# r202smt.net
KiCad netlist of a schematic drawn in EAGLE
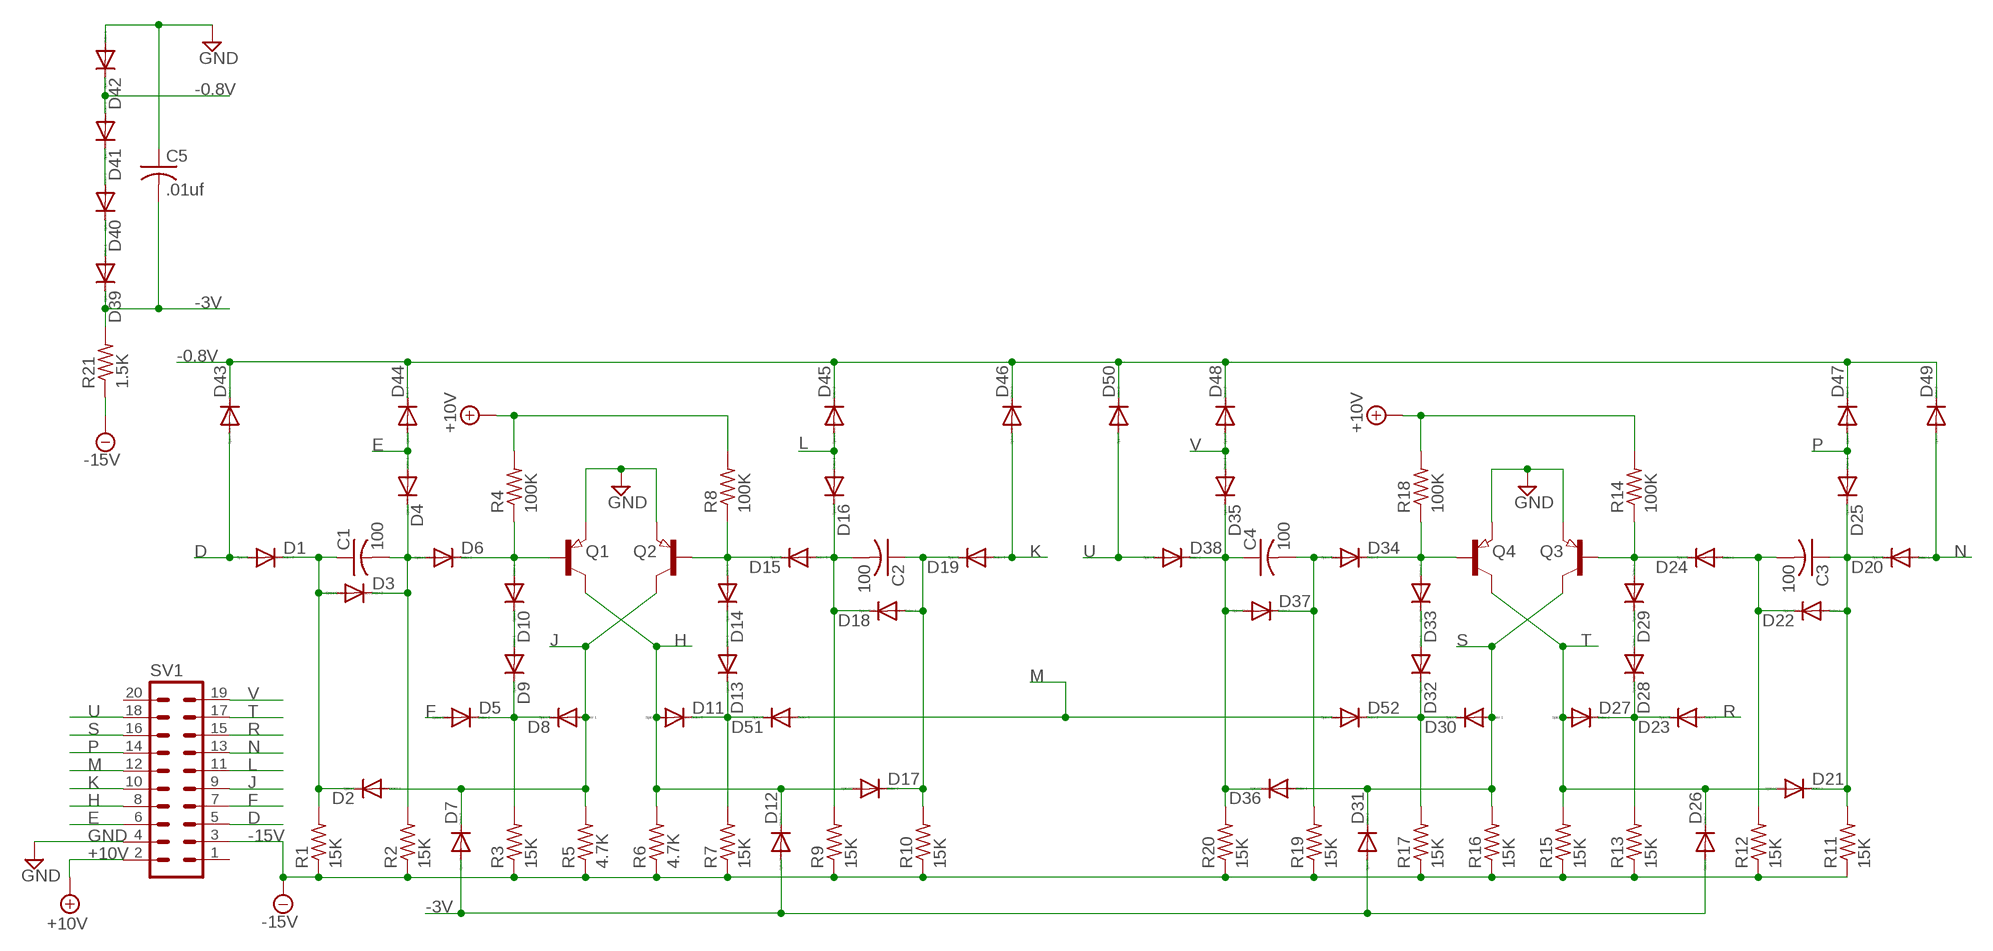
[diagram p0: schematic, sheet 1]

(export (version "E")
  (design (tool "Eeschema 10.0.6"))
  (components
    (comp (ref "C1")
      (value "100")
      (footprint "eagle-import:C0603")
      (libsource (lib "eagle-import") (part "C-USC0603"))
    )
    (comp (ref "C2")
      (value "100")
      (footprint "eagle-import:C0603")
      (libsource (lib "eagle-import") (part "C-USC0603"))
    )
    (comp (ref "C3")
      (value "100")
      (footprint "eagle-import:C0603")
      (libsource (lib "eagle-import") (part "C-USC0603"))
    )
    (comp (ref "C4")
      (value "100")
      (footprint "eagle-import:C0603")
      (libsource (lib "eagle-import") (part "C-USC0603"))
    )
    (comp (ref "C5")
      (value ".01uf")
      (footprint "eagle-import:C1206")
      (libsource (lib "eagle-import") (part "C-USC1206"))
    )
    (comp (ref "D1")
      (value "DIODE-SOD110-W")
      (footprint "eagle-import:SOD110-W")
      (libsource (lib "eagle-import") (part "DIODE-SOD110-W"))
    )
    (comp (ref "D2")
      (value "DIODE-SOD110-W")
      (footprint "eagle-import:SOD110-W")
      (libsource (lib "eagle-import") (part "DIODE-SOD110-W"))
    )
    (comp (ref "D3")
      (value "DIODE-SOD110-W")
      (footprint "eagle-import:SOD110-W")
      (libsource (lib "eagle-import") (part "DIODE-SOD110-W"))
    )
    (comp (ref "D4")
      (value "DIODE-SOD110-W")
      (footprint "eagle-import:SOD110-W")
      (libsource (lib "eagle-import") (part "DIODE-SOD110-W"))
    )
    (comp (ref "D5")
      (value "DIODE-SOD110-W")
      (footprint "eagle-import:SOD110-W")
      (libsource (lib "eagle-import") (part "DIODE-SOD110-W"))
    )
    (comp (ref "D6")
      (value "DIODE-SOD110-W")
      (footprint "eagle-import:SOD110-W")
      (libsource (lib "eagle-import") (part "DIODE-SOD110-W"))
    )
    (comp (ref "D7")
      (value "DIODE-SOD110-W")
      (footprint "eagle-import:SOD110-W")
      (libsource (lib "eagle-import") (part "DIODE-SOD110-W"))
    )
    (comp (ref "D8")
      (value "DIODE-SOD110-W")
      (footprint "eagle-import:SOD110-W")
      (libsource (lib "eagle-import") (part "DIODE-SOD110-W"))
    )
    (comp (ref "D9")
      (value "DIODE-SOD110-W")
      (footprint "eagle-import:SOD110-W")
      (libsource (lib "eagle-import") (part "DIODE-SOD110-W"))
    )
    (comp (ref "D10")
      (value "DIODE-SOD110-W")
      (footprint "eagle-import:SOD110-W")
      (libsource (lib "eagle-import") (part "DIODE-SOD110-W"))
    )
    (comp (ref "D11")
      (value "DIODE-SOD110-W")
      (footprint "eagle-import:SOD110-W")
      (libsource (lib "eagle-import") (part "DIODE-SOD110-W"))
    )
    (comp (ref "D12")
      (value "DIODE-SOD110-W")
      (footprint "eagle-import:SOD110-W")
      (libsource (lib "eagle-import") (part "DIODE-SOD110-W"))
    )
    (comp (ref "D13")
      (value "DIODE-SOD110-W")
      (footprint "eagle-import:SOD110-W")
      (libsource (lib "eagle-import") (part "DIODE-SOD110-W"))
    )
    (comp (ref "D14")
      (value "DIODE-SOD110-W")
      (footprint "eagle-import:SOD110-W")
      (libsource (lib "eagle-import") (part "DIODE-SOD110-W"))
    )
    (comp (ref "D15")
      (value "DIODE-SOD110-W")
      (footprint "eagle-import:SOD110-W")
      (libsource (lib "eagle-import") (part "DIODE-SOD110-W"))
    )
    (comp (ref "D16")
      (value "DIODE-SOD110-W")
      (footprint "eagle-import:SOD110-W")
      (libsource (lib "eagle-import") (part "DIODE-SOD110-W"))
    )
    (comp (ref "D17")
      (value "DIODE-SOD110-W")
      (footprint "eagle-import:SOD110-W")
      (libsource (lib "eagle-import") (part "DIODE-SOD110-W"))
    )
    (comp (ref "D18")
      (value "DIODE-SOD110-W")
      (footprint "eagle-import:SOD110-W")
      (libsource (lib "eagle-import") (part "DIODE-SOD110-W"))
    )
    (comp (ref "D19")
      (value "DIODE-SOD110-W")
      (footprint "eagle-import:SOD110-W")
      (libsource (lib "eagle-import") (part "DIODE-SOD110-W"))
    )
    (comp (ref "D20")
      (value "DIODE-SOD110-W")
      (footprint "eagle-import:SOD110-W")
      (libsource (lib "eagle-import") (part "DIODE-SOD110-W"))
    )
    (comp (ref "D21")
      (value "DIODE-SOD110-W")
      (footprint "eagle-import:SOD110-W")
      (libsource (lib "eagle-import") (part "DIODE-SOD110-W"))
    )
    (comp (ref "D22")
      (value "DIODE-SOD110-W")
      (footprint "eagle-import:SOD110-W")
      (libsource (lib "eagle-import") (part "DIODE-SOD110-W"))
    )
    (comp (ref "D23")
      (value "DIODE-SOD110-W")
      (footprint "eagle-import:SOD110-W")
      (libsource (lib "eagle-import") (part "DIODE-SOD110-W"))
    )
    (comp (ref "D24")
      (value "DIODE-SOD110-W")
      (footprint "eagle-import:SOD110-W")
      (libsource (lib "eagle-import") (part "DIODE-SOD110-W"))
    )
    (comp (ref "D25")
      (value "DIODE-SOD110-W")
      (footprint "eagle-import:SOD110-W")
      (libsource (lib "eagle-import") (part "DIODE-SOD110-W"))
    )
    (comp (ref "D26")
      (value "DIODE-SOD110-W")
      (footprint "eagle-import:SOD110-W")
      (libsource (lib "eagle-import") (part "DIODE-SOD110-W"))
    )
    (comp (ref "D27")
      (value "DIODE-SOD110-W")
      (footprint "eagle-import:SOD110-W")
      (libsource (lib "eagle-import") (part "DIODE-SOD110-W"))
    )
    (comp (ref "D28")
      (value "DIODE-SOD110-W")
      (footprint "eagle-import:SOD110-W")
      (libsource (lib "eagle-import") (part "DIODE-SOD110-W"))
    )
    (comp (ref "D29")
      (value "DIODE-SOD110-W")
      (footprint "eagle-import:SOD110-W")
      (libsource (lib "eagle-import") (part "DIODE-SOD110-W"))
    )
    (comp (ref "D30")
      (value "DIODE-SOD110-W")
      (footprint "eagle-import:SOD110-W")
      (libsource (lib "eagle-import") (part "DIODE-SOD110-W"))
    )
    (comp (ref "D31")
      (value "DIODE-SOD110-W")
      (footprint "eagle-import:SOD110-W")
      (libsource (lib "eagle-import") (part "DIODE-SOD110-W"))
    )
    (comp (ref "D32")
      (value "DIODE-SOD110-W")
      (footprint "eagle-import:SOD110-W")
      (libsource (lib "eagle-import") (part "DIODE-SOD110-W"))
    )
    (comp (ref "D33")
      (value "DIODE-SOD110-W")
      (footprint "eagle-import:SOD110-W")
      (libsource (lib "eagle-import") (part "DIODE-SOD110-W"))
    )
    (comp (ref "D34")
      (value "DIODE-SOD110-W")
      (footprint "eagle-import:SOD110-W")
      (libsource (lib "eagle-import") (part "DIODE-SOD110-W"))
    )
    (comp (ref "D35")
      (value "DIODE-SOD110-W")
      (footprint "eagle-import:SOD110-W")
      (libsource (lib "eagle-import") (part "DIODE-SOD110-W"))
    )
    (comp (ref "D36")
      (value "DIODE-SOD110-W")
      (footprint "eagle-import:SOD110-W")
      (libsource (lib "eagle-import") (part "DIODE-SOD110-W"))
    )
    (comp (ref "D37")
      (value "DIODE-SOD110-W")
      (footprint "eagle-import:SOD110-W")
      (libsource (lib "eagle-import") (part "DIODE-SOD110-W"))
    )
    (comp (ref "D38")
      (value "DIODE-SOD110-W")
      (footprint "eagle-import:SOD110-W")
      (libsource (lib "eagle-import") (part "DIODE-SOD110-W"))
    )
    (comp (ref "D39")
      (value "DIODE-SOD110-W")
      (footprint "eagle-import:SOD110-W")
      (libsource (lib "eagle-import") (part "DIODE-SOD110-W"))
    )
    (comp (ref "D40")
      (value "DIODE-SOD110-W")
      (footprint "eagle-import:SOD110-W")
      (libsource (lib "eagle-import") (part "DIODE-SOD110-W"))
    )
    (comp (ref "D41")
      (value "DIODE-SOD110-W")
      (footprint "eagle-import:SOD110-W")
      (libsource (lib "eagle-import") (part "DIODE-SOD110-W"))
    )
    (comp (ref "D42")
      (value "DIODE-SOD110-W")
      (footprint "eagle-import:SOD110-W")
      (libsource (lib "eagle-import") (part "DIODE-SOD110-W"))
    )
    (comp (ref "D43")
      (value "DIODE-SOD110-W")
      (footprint "eagle-import:SOD110-W")
      (libsource (lib "eagle-import") (part "DIODE-SOD110-W"))
    )
    (comp (ref "D44")
      (value "DIODE-SOD110-W")
      (footprint "eagle-import:SOD110-W")
      (libsource (lib "eagle-import") (part "DIODE-SOD110-W"))
    )
    (comp (ref "D45")
      (value "DIODE-SOD110-W")
      (footprint "eagle-import:SOD110-W")
      (libsource (lib "eagle-import") (part "DIODE-SOD110-W"))
    )
    (comp (ref "D46")
      (value "DIODE-SOD110-W")
      (footprint "eagle-import:SOD110-W")
      (libsource (lib "eagle-import") (part "DIODE-SOD110-W"))
    )
    (comp (ref "D47")
      (value "DIODE-SOD110-W")
      (footprint "eagle-import:SOD110-W")
      (libsource (lib "eagle-import") (part "DIODE-SOD110-W"))
    )
    (comp (ref "D48")
      (value "DIODE-SOD110-W")
      (footprint "eagle-import:SOD110-W")
      (libsource (lib "eagle-import") (part "DIODE-SOD110-W"))
    )
    (comp (ref "D49")
      (value "DIODE-SOD110-W")
      (footprint "eagle-import:SOD110-W")
      (libsource (lib "eagle-import") (part "DIODE-SOD110-W"))
    )
    (comp (ref "D50")
      (value "DIODE-SOD110-W")
      (footprint "eagle-import:SOD110-W")
      (libsource (lib "eagle-import") (part "DIODE-SOD110-W"))
    )
    (comp (ref "D51")
      (value "DIODE-SOD110-W")
      (footprint "eagle-import:SOD110-W")
      (libsource (lib "eagle-import") (part "DIODE-SOD110-W"))
    )
    (comp (ref "D52")
      (value "DIODE-SOD110-W")
      (footprint "eagle-import:SOD110-W")
      (libsource (lib "eagle-import") (part "DIODE-SOD110-W"))
    )
    (comp (ref "Q1")
      (value "PNP-TRANSISTOR_SOT23")
      (footprint "eagle-import:SOT23")
      (libsource (lib "eagle-import") (part "PNP-TRANSISTOR_SOT23"))
    )
    (comp (ref "Q2")
      (value "PNP-TRANSISTOR_SOT23")
      (footprint "eagle-import:SOT23")
      (libsource (lib "eagle-import") (part "PNP-TRANSISTOR_SOT23"))
    )
    (comp (ref "Q3")
      (value "PNP-TRANSISTOR_SOT23")
      (footprint "eagle-import:SOT23")
      (libsource (lib "eagle-import") (part "PNP-TRANSISTOR_SOT23"))
    )
    (comp (ref "Q4")
      (value "PNP-TRANSISTOR_SOT23")
      (footprint "eagle-import:SOT23")
      (libsource (lib "eagle-import") (part "PNP-TRANSISTOR_SOT23"))
    )
    (comp (ref "R1")
      (value "15K")
      (footprint "eagle-import:R0603")
      (libsource (lib "eagle-import") (part "R-US_R0603"))
    )
    (comp (ref "R2")
      (value "15K")
      (footprint "eagle-import:R0603")
      (libsource (lib "eagle-import") (part "R-US_R0603"))
    )
    (comp (ref "R3")
      (value "15K")
      (footprint "eagle-import:R0603")
      (libsource (lib "eagle-import") (part "R-US_R0603"))
    )
    (comp (ref "R4")
      (value "100K")
      (footprint "eagle-import:R0603")
      (libsource (lib "eagle-import") (part "R-US_R0603"))
    )
    (comp (ref "R5")
      (value "4.7K")
      (footprint "eagle-import:R0603")
      (libsource (lib "eagle-import") (part "R-US_R0603"))
    )
    (comp (ref "R6")
      (value "4.7K")
      (footprint "eagle-import:R0603")
      (libsource (lib "eagle-import") (part "R-US_R0603"))
    )
    (comp (ref "R7")
      (value "15K")
      (footprint "eagle-import:R0603")
      (libsource (lib "eagle-import") (part "R-US_R0603"))
    )
    (comp (ref "R8")
      (value "100K")
      (footprint "eagle-import:R0603")
      (libsource (lib "eagle-import") (part "R-US_R0603"))
    )
    (comp (ref "R9")
      (value "15K")
      (footprint "eagle-import:R0603")
      (libsource (lib "eagle-import") (part "R-US_R0603"))
    )
    (comp (ref "R10")
      (value "15K")
      (footprint "eagle-import:R0603")
      (libsource (lib "eagle-import") (part "R-US_R0603"))
    )
    (comp (ref "R11")
      (value "15K")
      (footprint "eagle-import:R0603")
      (libsource (lib "eagle-import") (part "R-US_R0603"))
    )
    (comp (ref "R12")
      (value "15K")
      (footprint "eagle-import:R0603")
      (libsource (lib "eagle-import") (part "R-US_R0603"))
    )
    (comp (ref "R13")
      (value "15K")
      (footprint "eagle-import:R0603")
      (libsource (lib "eagle-import") (part "R-US_R0603"))
    )
    (comp (ref "R14")
      (value "100K")
      (footprint "eagle-import:R0603")
      (libsource (lib "eagle-import") (part "R-US_R0603"))
    )
    (comp (ref "R15")
      (value "15K")
      (footprint "eagle-import:R0603")
      (libsource (lib "eagle-import") (part "R-US_R0603"))
    )
    (comp (ref "R16")
      (value "15K")
      (footprint "eagle-import:R0603")
      (libsource (lib "eagle-import") (part "R-US_R0603"))
    )
    (comp (ref "R17")
      (value "15K")
      (footprint "eagle-import:R0603")
      (libsource (lib "eagle-import") (part "R-US_R0603"))
    )
    (comp (ref "R18")
      (value "100K")
      (footprint "eagle-import:R0603")
      (libsource (lib "eagle-import") (part "R-US_R0603"))
    )
    (comp (ref "R19")
      (value "15K")
      (footprint "eagle-import:R0603")
      (libsource (lib "eagle-import") (part "R-US_R0603"))
    )
    (comp (ref "R20")
      (value "15K")
      (footprint "eagle-import:R0603")
      (libsource (lib "eagle-import") (part "R-US_R0603"))
    )
    (comp (ref "R21")
      (value "1.5K")
      (footprint "eagle-import:R1206")
      (libsource (lib "eagle-import") (part "R-US_R1206"))
    )
    (comp (ref "SV1")
      (value "MA10-2W")
      (footprint "eagle-import:MA10-2W")
      (libsource (lib "eagle-import") (part "MA10-2W"))
    )
  )
  (nets
    (net (code "1") (name "+10V") (class "Default")
      (node (ref "R14") (pin "2") (pinfunction "2_2") (pintype "passive"))
      (node (ref "R18") (pin "2") (pinfunction "2_2") (pintype "passive"))
      (node (ref "R4") (pin "2") (pinfunction "2_2") (pintype "passive"))
      (node (ref "R8") (pin "2") (pinfunction "2_2") (pintype "passive"))
      (node (ref "SV1") (pin "2") (pinfunction "2_2") (pintype "passive"))
    )
    (net (code "2") (name "-15V") (class "Default")
      (node (ref "R1") (pin "1") (pinfunction "1_1") (pintype "passive"))
      (node (ref "R10") (pin "1") (pinfunction "1_1") (pintype "passive"))
      (node (ref "R11") (pin "1") (pinfunction "1_1") (pintype "passive"))
      (node (ref "R12") (pin "1") (pinfunction "1_1") (pintype "passive"))
      (node (ref "R13") (pin "1") (pinfunction "1_1") (pintype "passive"))
      (node (ref "R15") (pin "1") (pinfunction "1_1") (pintype "passive"))
      (node (ref "R16") (pin "1") (pinfunction "1_1") (pintype "passive"))
      (node (ref "R17") (pin "1") (pinfunction "1_1") (pintype "passive"))
      (node (ref "R19") (pin "1") (pinfunction "1_1") (pintype "passive"))
      (node (ref "R2") (pin "1") (pinfunction "1_1") (pintype "passive"))
      (node (ref "R20") (pin "1") (pinfunction "1_1") (pintype "passive"))
      (node (ref "R21") (pin "1") (pinfunction "1_1") (pintype "passive"))
      (node (ref "R3") (pin "1") (pinfunction "1_1") (pintype "passive"))
      (node (ref "R5") (pin "1") (pinfunction "1_1") (pintype "passive"))
      (node (ref "R6") (pin "1") (pinfunction "1_1") (pintype "passive"))
      (node (ref "R7") (pin "1") (pinfunction "1_1") (pintype "passive"))
      (node (ref "R9") (pin "1") (pinfunction "1_1") (pintype "passive"))
      (node (ref "SV1") (pin "3") (pinfunction "3_3") (pintype "passive"))
    )
    (net (code "3") (name "/-0.8V") (class "Default")
      (node (ref "D41") (pin "A") (pinfunction "A_A") (pintype "passive"))
      (node (ref "D42") (pin "C") (pinfunction "C_C") (pintype "passive"))
      (node (ref "D43") (pin "C") (pinfunction "C_C") (pintype "passive"))
      (node (ref "D44") (pin "C") (pinfunction "C_C") (pintype "passive"))
      (node (ref "D45") (pin "C") (pinfunction "C_C") (pintype "passive"))
      (node (ref "D46") (pin "C") (pinfunction "C_C") (pintype "passive"))
      (node (ref "D47") (pin "C") (pinfunction "C_C") (pintype "passive"))
      (node (ref "D48") (pin "C") (pinfunction "C_C") (pintype "passive"))
      (node (ref "D49") (pin "C") (pinfunction "C_C") (pintype "passive"))
      (node (ref "D50") (pin "C") (pinfunction "C_C") (pintype "passive"))
    )
    (net (code "4") (name "/-3V") (class "Default")
      (node (ref "C5") (pin "2") (pinfunction "2_2") (pintype "passive"))
      (node (ref "D12") (pin "A") (pinfunction "A_A") (pintype "passive"))
      (node (ref "D26") (pin "A") (pinfunction "A_A") (pintype "passive"))
      (node (ref "D31") (pin "A") (pinfunction "A_A") (pintype "passive"))
      (node (ref "D39") (pin "C") (pinfunction "C_C") (pintype "passive"))
      (node (ref "D7") (pin "A") (pinfunction "A_A") (pintype "passive"))
      (node (ref "R21") (pin "2") (pinfunction "2_2") (pintype "passive"))
    )
    (net (code "5") (name "/D") (class "Default")
      (node (ref "D1") (pin "A") (pinfunction "A_A") (pintype "passive"))
      (node (ref "D43") (pin "A") (pinfunction "A_A") (pintype "passive"))
      (node (ref "SV1") (pin "5") (pinfunction "5_5") (pintype "passive"))
    )
    (net (code "6") (name "/E") (class "Default")
      (node (ref "D4") (pin "A") (pinfunction "A_A") (pintype "passive"))
      (node (ref "D44") (pin "A") (pinfunction "A_A") (pintype "passive"))
      (node (ref "SV1") (pin "6") (pinfunction "6_6") (pintype "passive"))
    )
    (net (code "7") (name "/F") (class "Default")
      (node (ref "D5") (pin "A") (pinfunction "A_A") (pintype "passive"))
      (node (ref "SV1") (pin "7") (pinfunction "7_7") (pintype "passive"))
    )
    (net (code "8") (name "/H") (class "Default")
      (node (ref "D11") (pin "A") (pinfunction "A_A") (pintype "passive"))
      (node (ref "D12") (pin "C") (pinfunction "C_C") (pintype "passive"))
      (node (ref "D17") (pin "A") (pinfunction "A_A") (pintype "passive"))
      (node (ref "Q1") (pin "3") (pinfunction "C_3") (pintype "passive"))
      (node (ref "R6") (pin "2") (pinfunction "2_2") (pintype "passive"))
      (node (ref "SV1") (pin "8") (pinfunction "8_8") (pintype "passive"))
    )
    (net (code "9") (name "/J") (class "Default")
      (node (ref "D2") (pin "A") (pinfunction "A_A") (pintype "passive"))
      (node (ref "D7") (pin "C") (pinfunction "C_C") (pintype "passive"))
      (node (ref "D8") (pin "A") (pinfunction "A_A") (pintype "passive"))
      (node (ref "Q2") (pin "3") (pinfunction "C_3") (pintype "passive"))
      (node (ref "R5") (pin "2") (pinfunction "2_2") (pintype "passive"))
      (node (ref "SV1") (pin "9") (pinfunction "9_9") (pintype "passive"))
    )
    (net (code "10") (name "/K") (class "Default")
      (node (ref "D19") (pin "A") (pinfunction "A_A") (pintype "passive"))
      (node (ref "D46") (pin "A") (pinfunction "A_A") (pintype "passive"))
      (node (ref "SV1") (pin "10") (pinfunction "10_10") (pintype "passive"))
    )
    (net (code "11") (name "/L") (class "Default")
      (node (ref "D16") (pin "A") (pinfunction "A_A") (pintype "passive"))
      (node (ref "D45") (pin "A") (pinfunction "A_A") (pintype "passive"))
      (node (ref "SV1") (pin "11") (pinfunction "11_11") (pintype "passive"))
    )
    (net (code "12") (name "/M") (class "Default")
      (node (ref "D51") (pin "A") (pinfunction "A_A") (pintype "passive"))
      (node (ref "D52") (pin "A") (pinfunction "A_A") (pintype "passive"))
      (node (ref "SV1") (pin "12") (pinfunction "12_12") (pintype "passive"))
    )
    (net (code "13") (name "/N") (class "Default")
      (node (ref "D20") (pin "A") (pinfunction "A_A") (pintype "passive"))
      (node (ref "D49") (pin "A") (pinfunction "A_A") (pintype "passive"))
      (node (ref "SV1") (pin "13") (pinfunction "13_13") (pintype "passive"))
    )
    (net (code "14") (name "/P") (class "Default")
      (node (ref "D25") (pin "A") (pinfunction "A_A") (pintype "passive"))
      (node (ref "D47") (pin "A") (pinfunction "A_A") (pintype "passive"))
      (node (ref "SV1") (pin "14") (pinfunction "14_14") (pintype "passive"))
    )
    (net (code "15") (name "/R") (class "Default")
      (node (ref "D23") (pin "A") (pinfunction "A_A") (pintype "passive"))
      (node (ref "SV1") (pin "15") (pinfunction "15_15") (pintype "passive"))
    )
    (net (code "16") (name "/S") (class "Default")
      (node (ref "D30") (pin "A") (pinfunction "A_A") (pintype "passive"))
      (node (ref "D31") (pin "C") (pinfunction "C_C") (pintype "passive"))
      (node (ref "D36") (pin "A") (pinfunction "A_A") (pintype "passive"))
      (node (ref "Q3") (pin "3") (pinfunction "C_3") (pintype "passive"))
      (node (ref "R16") (pin "2") (pinfunction "2_2") (pintype "passive"))
      (node (ref "SV1") (pin "16") (pinfunction "16_16") (pintype "passive"))
    )
    (net (code "17") (name "/T") (class "Default")
      (node (ref "D21") (pin "A") (pinfunction "A_A") (pintype "passive"))
      (node (ref "D26") (pin "C") (pinfunction "C_C") (pintype "passive"))
      (node (ref "D27") (pin "A") (pinfunction "A_A") (pintype "passive"))
      (node (ref "Q4") (pin "3") (pinfunction "C_3") (pintype "passive"))
      (node (ref "R15") (pin "2") (pinfunction "2_2") (pintype "passive"))
      (node (ref "SV1") (pin "17") (pinfunction "17_17") (pintype "passive"))
    )
    (net (code "18") (name "/U") (class "Default")
      (node (ref "D38") (pin "A") (pinfunction "A_A") (pintype "passive"))
      (node (ref "D50") (pin "A") (pinfunction "A_A") (pintype "passive"))
      (node (ref "SV1") (pin "18") (pinfunction "18_18") (pintype "passive"))
    )
    (net (code "19") (name "/V") (class "Default")
      (node (ref "D35") (pin "A") (pinfunction "A_A") (pintype "passive"))
      (node (ref "D48") (pin "A") (pinfunction "A_A") (pintype "passive"))
      (node (ref "SV1") (pin "19") (pinfunction "19_19") (pintype "passive"))
    )
    (net (code "20") (name "GND") (class "Default")
      (node (ref "C5") (pin "1") (pinfunction "1_1") (pintype "passive"))
      (node (ref "D42") (pin "A") (pinfunction "A_A") (pintype "passive"))
      (node (ref "Q1") (pin "2") (pinfunction "E_2") (pintype "passive"))
      (node (ref "Q2") (pin "2") (pinfunction "E_2") (pintype "passive"))
      (node (ref "Q3") (pin "2") (pinfunction "E_2") (pintype "passive"))
      (node (ref "Q4") (pin "2") (pinfunction "E_2") (pintype "passive"))
      (node (ref "SV1") (pin "4") (pinfunction "4_4") (pintype "passive"))
    )
    (net (code "21") (name "Net-(C1-Pad1)") (class "Default")
      (node (ref "C1") (pin "1") (pinfunction "1_1") (pintype "passive"))
      (node (ref "D1") (pin "C") (pinfunction "C_C") (pintype "passive"))
      (node (ref "D2") (pin "C") (pinfunction "C_C") (pintype "passive"))
      (node (ref "D3") (pin "A") (pinfunction "A_A") (pintype "passive"))
      (node (ref "R1") (pin "2") (pinfunction "2_2") (pintype "passive"))
    )
    (net (code "22") (name "Net-(C1-Pad2)") (class "Default")
      (node (ref "C1") (pin "2") (pinfunction "2_2") (pintype "passive"))
      (node (ref "D3") (pin "C") (pinfunction "C_C") (pintype "passive"))
      (node (ref "D4") (pin "C") (pinfunction "C_C") (pintype "passive"))
      (node (ref "D6") (pin "A") (pinfunction "A_A") (pintype "passive"))
      (node (ref "R2") (pin "2") (pinfunction "2_2") (pintype "passive"))
    )
    (net (code "23") (name "Net-(C2-Pad1)") (class "Default")
      (node (ref "C2") (pin "1") (pinfunction "1_1") (pintype "passive"))
      (node (ref "D17") (pin "C") (pinfunction "C_C") (pintype "passive"))
      (node (ref "D18") (pin "A") (pinfunction "A_A") (pintype "passive"))
      (node (ref "D19") (pin "C") (pinfunction "C_C") (pintype "passive"))
      (node (ref "R10") (pin "2") (pinfunction "2_2") (pintype "passive"))
    )
    (net (code "24") (name "Net-(C2-Pad2)") (class "Default")
      (node (ref "C2") (pin "2") (pinfunction "2_2") (pintype "passive"))
      (node (ref "D15") (pin "A") (pinfunction "A_A") (pintype "passive"))
      (node (ref "D16") (pin "C") (pinfunction "C_C") (pintype "passive"))
      (node (ref "D18") (pin "C") (pinfunction "C_C") (pintype "passive"))
      (node (ref "R9") (pin "2") (pinfunction "2_2") (pintype "passive"))
    )
    (net (code "25") (name "Net-(C3-Pad1)") (class "Default")
      (node (ref "C3") (pin "1") (pinfunction "1_1") (pintype "passive"))
      (node (ref "D20") (pin "C") (pinfunction "C_C") (pintype "passive"))
      (node (ref "D21") (pin "C") (pinfunction "C_C") (pintype "passive"))
      (node (ref "D22") (pin "A") (pinfunction "A_A") (pintype "passive"))
      (node (ref "D25") (pin "C") (pinfunction "C_C") (pintype "passive"))
      (node (ref "R11") (pin "2") (pinfunction "2_2") (pintype "passive"))
    )
    (net (code "26") (name "Net-(C3-Pad2)") (class "Default")
      (node (ref "C3") (pin "2") (pinfunction "2_2") (pintype "passive"))
      (node (ref "D22") (pin "C") (pinfunction "C_C") (pintype "passive"))
      (node (ref "D24") (pin "A") (pinfunction "A_A") (pintype "passive"))
      (node (ref "R12") (pin "2") (pinfunction "2_2") (pintype "passive"))
    )
    (net (code "27") (name "Net-(C4-Pad1)") (class "Default")
      (node (ref "C4") (pin "1") (pinfunction "1_1") (pintype "passive"))
      (node (ref "D35") (pin "C") (pinfunction "C_C") (pintype "passive"))
      (node (ref "D36") (pin "C") (pinfunction "C_C") (pintype "passive"))
      (node (ref "D37") (pin "A") (pinfunction "A_A") (pintype "passive"))
      (node (ref "D38") (pin "C") (pinfunction "C_C") (pintype "passive"))
      (node (ref "R20") (pin "2") (pinfunction "2_2") (pintype "passive"))
    )
    (net (code "28") (name "Net-(C4-Pad2)") (class "Default")
      (node (ref "C4") (pin "2") (pinfunction "2_2") (pintype "passive"))
      (node (ref "D34") (pin "A") (pinfunction "A_A") (pintype "passive"))
      (node (ref "D37") (pin "C") (pinfunction "C_C") (pintype "passive"))
      (node (ref "R19") (pin "2") (pinfunction "2_2") (pintype "passive"))
    )
    (net (code "29") (name "Net-(D5-PadC)") (class "Default")
      (node (ref "D5") (pin "C") (pinfunction "C_C") (pintype "passive"))
      (node (ref "D8") (pin "C") (pinfunction "C_C") (pintype "passive"))
      (node (ref "D9") (pin "C") (pinfunction "C_C") (pintype "passive"))
      (node (ref "R3") (pin "2") (pinfunction "2_2") (pintype "passive"))
    )
    (net (code "30") (name "Net-(D10-PadC)") (class "Default")
      (node (ref "D10") (pin "C") (pinfunction "C_C") (pintype "passive"))
      (node (ref "D9") (pin "A") (pinfunction "A_A") (pintype "passive"))
    )
    (net (code "31") (name "Net-(D11-PadC)") (class "Default")
      (node (ref "D11") (pin "C") (pinfunction "C_C") (pintype "passive"))
      (node (ref "D13") (pin "C") (pinfunction "C_C") (pintype "passive"))
      (node (ref "D51") (pin "C") (pinfunction "C_C") (pintype "passive"))
      (node (ref "R7") (pin "2") (pinfunction "2_2") (pintype "passive"))
    )
    (net (code "32") (name "Net-(D13-PadA)") (class "Default")
      (node (ref "D13") (pin "A") (pinfunction "A_A") (pintype "passive"))
      (node (ref "D14") (pin "C") (pinfunction "C_C") (pintype "passive"))
    )
    (net (code "33") (name "Net-(D23-PadC)") (class "Default")
      (node (ref "D23") (pin "C") (pinfunction "C_C") (pintype "passive"))
      (node (ref "D27") (pin "C") (pinfunction "C_C") (pintype "passive"))
      (node (ref "D28") (pin "C") (pinfunction "C_C") (pintype "passive"))
      (node (ref "R13") (pin "2") (pinfunction "2_2") (pintype "passive"))
    )
    (net (code "34") (name "Net-(D28-PadA)") (class "Default")
      (node (ref "D28") (pin "A") (pinfunction "A_A") (pintype "passive"))
      (node (ref "D29") (pin "C") (pinfunction "C_C") (pintype "passive"))
    )
    (net (code "35") (name "Net-(D30-PadC)") (class "Default")
      (node (ref "D30") (pin "C") (pinfunction "C_C") (pintype "passive"))
      (node (ref "D32") (pin "C") (pinfunction "C_C") (pintype "passive"))
      (node (ref "D52") (pin "C") (pinfunction "C_C") (pintype "passive"))
      (node (ref "R17") (pin "2") (pinfunction "2_2") (pintype "passive"))
    )
    (net (code "36") (name "Net-(D32-PadA)") (class "Default")
      (node (ref "D32") (pin "A") (pinfunction "A_A") (pintype "passive"))
      (node (ref "D33") (pin "C") (pinfunction "C_C") (pintype "passive"))
    )
    (net (code "37") (name "Net-(D39-PadA)") (class "Default")
      (node (ref "D39") (pin "A") (pinfunction "A_A") (pintype "passive"))
      (node (ref "D40") (pin "C") (pinfunction "C_C") (pintype "passive"))
    )
    (net (code "38") (name "Net-(D40-PadA)") (class "Default")
      (node (ref "D40") (pin "A") (pinfunction "A_A") (pintype "passive"))
      (node (ref "D41") (pin "C") (pinfunction "C_C") (pintype "passive"))
    )
    (net (code "39") (name "Net-(Q1-B)") (class "Default")
      (node (ref "D10") (pin "A") (pinfunction "A_A") (pintype "passive"))
      (node (ref "D6") (pin "C") (pinfunction "C_C") (pintype "passive"))
      (node (ref "Q1") (pin "1") (pinfunction "B_1") (pintype "passive"))
      (node (ref "R4") (pin "1") (pinfunction "1_1") (pintype "passive"))
    )
    (net (code "40") (name "Net-(Q2-B)") (class "Default")
      (node (ref "D14") (pin "A") (pinfunction "A_A") (pintype "passive"))
      (node (ref "D15") (pin "C") (pinfunction "C_C") (pintype "passive"))
      (node (ref "Q2") (pin "1") (pinfunction "B_1") (pintype "passive"))
      (node (ref "R8") (pin "1") (pinfunction "1_1") (pintype "passive"))
    )
    (net (code "41") (name "Net-(Q3-B)") (class "Default")
      (node (ref "D24") (pin "C") (pinfunction "C_C") (pintype "passive"))
      (node (ref "D29") (pin "A") (pinfunction "A_A") (pintype "passive"))
      (node (ref "Q3") (pin "1") (pinfunction "B_1") (pintype "passive"))
      (node (ref "R14") (pin "1") (pinfunction "1_1") (pintype "passive"))
    )
    (net (code "42") (name "Net-(Q4-B)") (class "Default")
      (node (ref "D33") (pin "A") (pinfunction "A_A") (pintype "passive"))
      (node (ref "D34") (pin "C") (pinfunction "C_C") (pintype "passive"))
      (node (ref "Q4") (pin "1") (pinfunction "B_1") (pintype "passive"))
      (node (ref "R18") (pin "1") (pinfunction "1_1") (pintype "passive"))
    )
    (net (code "43") (name "unconnected-(SV1-Pad1)") (class "Default")
      (node (ref "SV1") (pin "1") (pinfunction "1_1") (pintype "passive"))
    )
    (net (code "44") (name "unconnected-(SV1-Pad20)") (class "Default")
      (node (ref "SV1") (pin "20") (pinfunction "20_20") (pintype "passive"))
    )
  )
)
